# StepDown_LM2596.net
KiCad netlist of a schematic drawn in Altium Designer
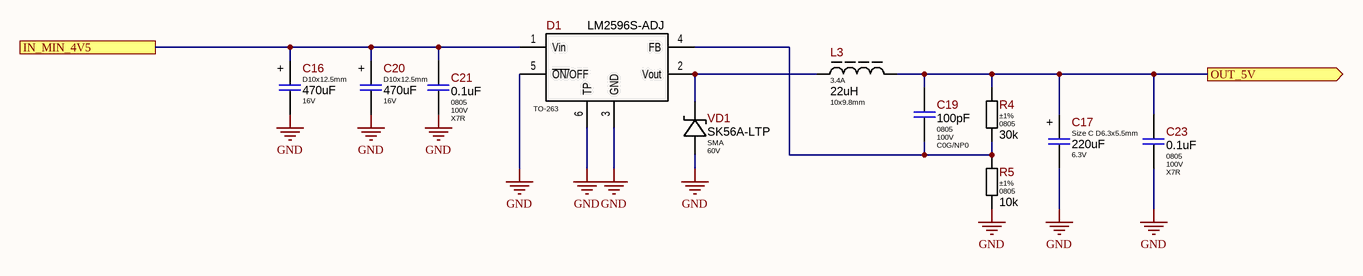
[diagram p0: StepDown_LM2596.SchDoc]

(export (version "E")
  (design (tool "Eeschema 10.0.6"))
  (components
    (comp (ref "C16")
      (value "470uF")
      (footprint "CAP-AE-PTH-100D10x125H15")
      (description "470uF 16V D10x12.5mm Electrolytic Low Impedance")
      (fields
        (field (name "PACKAGE") "D10x12.5mm")
        (field (name "VOLTAGE") "16V")
        (field (name "PART NUMBER") "EXR471M16B")
        (field (name "MANUFACTURER") "Hitano")
      )
      (libsource (lib "capacitors") (part "EXR471M16B"))
    )
    (comp (ref "C17")
      (value "220uF")
      (footprint "CAP-AE-660x550H20_MED")
      (description "220uF 6.3V ±20% Size C D6.3x5.5mm SMD Electrolytic Capacitor")
      (fields
        (field (name "PACKAGE") "Size C D6.3x5.5mm")
        (field (name "VOLTAGE") "6.3V")
        (field (name "PART NUMBER") "ELV221M0JRC")
        (field (name "MANUFACTURER") "Hitano")
      )
      (libsource (lib "capacitors") (part "ELV221M0JRC"))
    )
    (comp (ref "C19")
      (value "100pF")
      (footprint "CAP-0805(2012)X60T10")
      (description "100pF 100V C0G, NP0 ±5% 0805 Ceramic Capacitor RoHS")
      (fields
        (field (name "PACKAGE") "0805")
        (field (name "VOLTAGE") "100V")
        (field (name "DIELECTRIC TYPE") "C0G/NP0")
        (field (name "PART NUMBER") "CC0805JRNPO0BN101")
        (field (name "MANUFACTURER") "Yageo")
      )
      (libsource (lib "capacitors") (part "CC0805JRNPO0BN101"))
    )
    (comp (ref "C20")
      (value "470uF")
      (footprint "CAP-AE-PTH-100D10x125H15")
      (description "470uF 16V D10x12.5mm Electrolytic Low Impedance")
      (fields
        (field (name "PACKAGE") "D10x12.5mm")
        (field (name "VOLTAGE") "16V")
        (field (name "PART NUMBER") "EXR471M16B")
        (field (name "MANUFACTURER") "Hitano")
      )
      (libsource (lib "capacitors") (part "EXR471M16B"))
    )
    (comp (ref "C21")
      (value "0.1uF")
      (footprint "C_CERAMIC_0805_MED")
      (description "100nF 100V X7R ±10% 0805 Ceramic Capacitor RoHS")
      (fields
        (field (name "PACKAGE") "0805")
        (field (name "VOLTAGE") "100V")
        (field (name "DIELECTRIC TYPE") "X7R")
        (field (name "PART NUMBER") "CL21B104KCFSFNE")
        (field (name "MANUFACTURER") "Samsung Electro-Mechanics")
      )
      (libsource (lib "capacitors") (part "CL21B104KCFSFNE"))
    )
    (comp (ref "C23")
      (value "0.1uF")
      (footprint "C_CERAMIC_0805_MED")
      (description "100nF 100V X7R ±10% 0805 Ceramic Capacitor RoHS")
      (fields
        (field (name "PACKAGE") "0805")
        (field (name "VOLTAGE") "100V")
        (field (name "DIELECTRIC TYPE") "X7R")
        (field (name "PART NUMBER") "CL21B104KCFSFNE")
        (field (name "MANUFACTURER") "Samsung Electro-Mechanics")
      )
      (libsource (lib "capacitors") (part "CL21B104KCFSFNE"))
    )
    (comp (ref "D1")
      (value "LM2596S-ADJ")
      (footprint "TO-263-5-1")
      (description "SIMPLE SWITCHER Power Converter 150-kHz 3-A Step-Down Voltage Regulator")
      (fields
        (field (name "PACKAGE") "TO-263")
        (field (name "PART NUMBER") "LM2596S-ADJ")
        (field (name "MANUFACTURER") "Texas Instruments")
      )
      (libsource (lib "ic") (part "LM2596S-ADJ"))
    )
    (comp (ref "L3")
      (value "22uH")
      (footprint "SRN1060-Series")
      (description "22uH Semi-Shielded Wirewound Inductor 3.4A 53mOhm Max")
      (fields
        (field (name "CURRENT") "3.4A")
        (field (name "PACKAGE") "10x9.8mm")
        (field (name "PART NUMBER") "SRN1060-220M")
        (field (name "TOLERANCE") "±20%")
      )
      (libsource (lib "inductors") (part "SRN1060-220M"))
    )
    (comp (ref "R4")
      (value "30k")
      (footprint "R_ANY_CHIP_0805_MED")
      (description "30 kOhms ±1%, 1/8W 0805 Thick Film Resistor")
      (fields
        (field (name "TOLERANCE") "±1%")
        (field (name "PACKAGE") "0805")
        (field (name "PART NUMBER") "RC0805FR-0730KL")
        (field (name "MANUFACTURER") "Yageo")
      )
      (libsource (lib "resistors") (part "RC0805FR-0730KL"))
    )
    (comp (ref "R5")
      (value "10k")
      (footprint "R_ANY_CHIP_0805_MED")
      (description "10 kOhms ±1%, 1/8W 0805 Thick Film Resistor")
      (fields
        (field (name "TOLERANCE") "±1%")
        (field (name "PACKAGE") "0805")
        (field (name "PART NUMBER") "RC0805FR-0710K2L")
        (field (name "MANUFACTURER") "Yageo")
      )
      (libsource (lib "resistors") (part "RC0805FR-0710K2L"))
    )
    (comp (ref "VD1")
      (value "SK56A-LTP")
      (footprint "SMA_MED")
      (description "Diode Schottky 60V 5A, SMA")
      (fields
        (field (name "PART NUMBER") "SK56A-LTP")
        (field (name "PACKAGE") "SMA")
        (field (name "VOLTAGE") "60V")
        (field (name "MANUFACTURER") "Micro Commercial Components")
      )
      (libsource (lib "diodes") (part "SK56A-LTP"))
    )
  )
  (nets
    (net (code "1") (name "/IN_MIN_4V5") (class "Default")
      (node (ref "C16") (pin "1") (pinfunction "1_1") (pintype "passive"))
      (node (ref "C20") (pin "1") (pinfunction "1_1") (pintype "passive"))
      (node (ref "C21") (pin "1") (pinfunction "1_1") (pintype "passive"))
      (node (ref "D1") (pin "1") (pinfunction "Vin_1") (pintype "passive"))
    )
    (net (code "2") (name "/OUT_5V") (class "Default")
      (node (ref "C17") (pin "1") (pinfunction "1_1") (pintype "passive"))
      (node (ref "C19") (pin "2") (pinfunction "2_2") (pintype "passive"))
      (node (ref "C23") (pin "1") (pinfunction "1_1") (pintype "passive"))
      (node (ref "L3") (pin "2") (pintype "passive"))
      (node (ref "R4") (pin "1") (pintype "passive"))
    )
    (net (code "3") (name "GND") (class "Default")
      (node (ref "C16") (pin "2") (pinfunction "2_2") (pintype "passive"))
      (node (ref "C17") (pin "2") (pinfunction "2_2") (pintype "passive"))
      (node (ref "C20") (pin "2") (pinfunction "2_2") (pintype "passive"))
      (node (ref "C21") (pin "2") (pinfunction "2_2") (pintype "passive"))
      (node (ref "C23") (pin "2") (pinfunction "2_2") (pintype "passive"))
      (node (ref "D1") (pin "3") (pinfunction "GND_3") (pintype "passive"))
      (node (ref "D1") (pin "5") (pinfunction "~{ON/}OFF_5") (pintype "passive"))
      (node (ref "D1") (pin "6") (pinfunction "TP_6") (pintype "passive"))
      (node (ref "R5") (pin "2") (pintype "passive"))
      (node (ref "VD1") (pin "AN") (pintype "passive"))
    )
    (net (code "4") (name "Net-(D1-FB)") (class "Default")
      (node (ref "C19") (pin "1") (pinfunction "1_1") (pintype "passive"))
      (node (ref "D1") (pin "4") (pinfunction "FB_4") (pintype "passive"))
      (node (ref "R4") (pin "2") (pintype "passive"))
      (node (ref "R5") (pin "1") (pintype "passive"))
    )
    (net (code "5") (name "Net-(D1-Vout)") (class "Default")
      (node (ref "D1") (pin "2") (pinfunction "Vout_2") (pintype "passive"))
      (node (ref "L3") (pin "1") (pintype "passive"))
      (node (ref "VD1") (pin "CA") (pintype "passive"))
    )
  )
)
